# IMU.net
KiCad netlist of a schematic drawn in Altium Designer
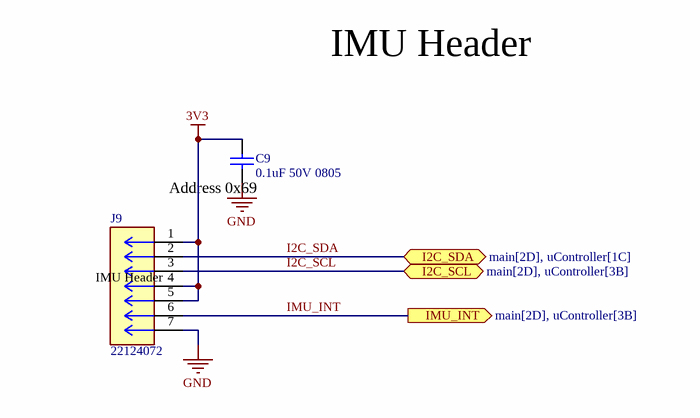
[diagram p0: IMU.SchDoc]

(export (version "E")
  (design (tool "Eeschema 10.0.6"))
  (components
    (comp (ref "C9")
      (value "0.1uF 50V 0805")
      (footprint "CAPC2012X14N")
      (description "Cap, SMD, 0.1uF, 50V, 10%, 0805, X7R")
      (fields
        (field (name "MANUFACTURER") "Samsung")
        (field (name "MANUFACTURERPARTNUMBER") "CL21B104KBCWPNC")
      )
      (libsource (lib "Andor Technology") (part "CAP"))
    )
    (comp (ref "J9")
      (value "22124072")
      (footprint "CONN_A-7395-07B_MOL")
      (libsource (lib "22124072") (part "22124072"))
    )
  )
  (nets
    (net (code "1") (name "/I2C_SCL") (class "Default")
      (node (ref "J9") (pin "3") (pinfunction "3_3") (pintype "passive"))
    )
    (net (code "2") (name "/I2C_SDA") (class "Default")
      (node (ref "J9") (pin "2") (pinfunction "2_2") (pintype "passive"))
    )
    (net (code "3") (name "/IMU_INT") (class "Default")
      (node (ref "J9") (pin "6") (pinfunction "6_6") (pintype "passive"))
    )
    (net (code "4") (name "3V3") (class "Default")
      (node (ref "C9") (pin "2") (pinfunction "2_2") (pintype "passive"))
      (node (ref "J9") (pin "1") (pinfunction "1_1") (pintype "passive"))
      (node (ref "J9") (pin "4") (pinfunction "4_4") (pintype "passive"))
      (node (ref "J9") (pin "5") (pinfunction "5_5") (pintype "passive"))
    )
    (net (code "5") (name "GND") (class "Default")
      (node (ref "C9") (pin "1") (pinfunction "1_1") (pintype "passive"))
      (node (ref "J9") (pin "7") (pinfunction "7_7") (pintype "passive"))
    )
  )
)
